# ENET.net
KiCad netlist of a schematic drawn in Altium Designer
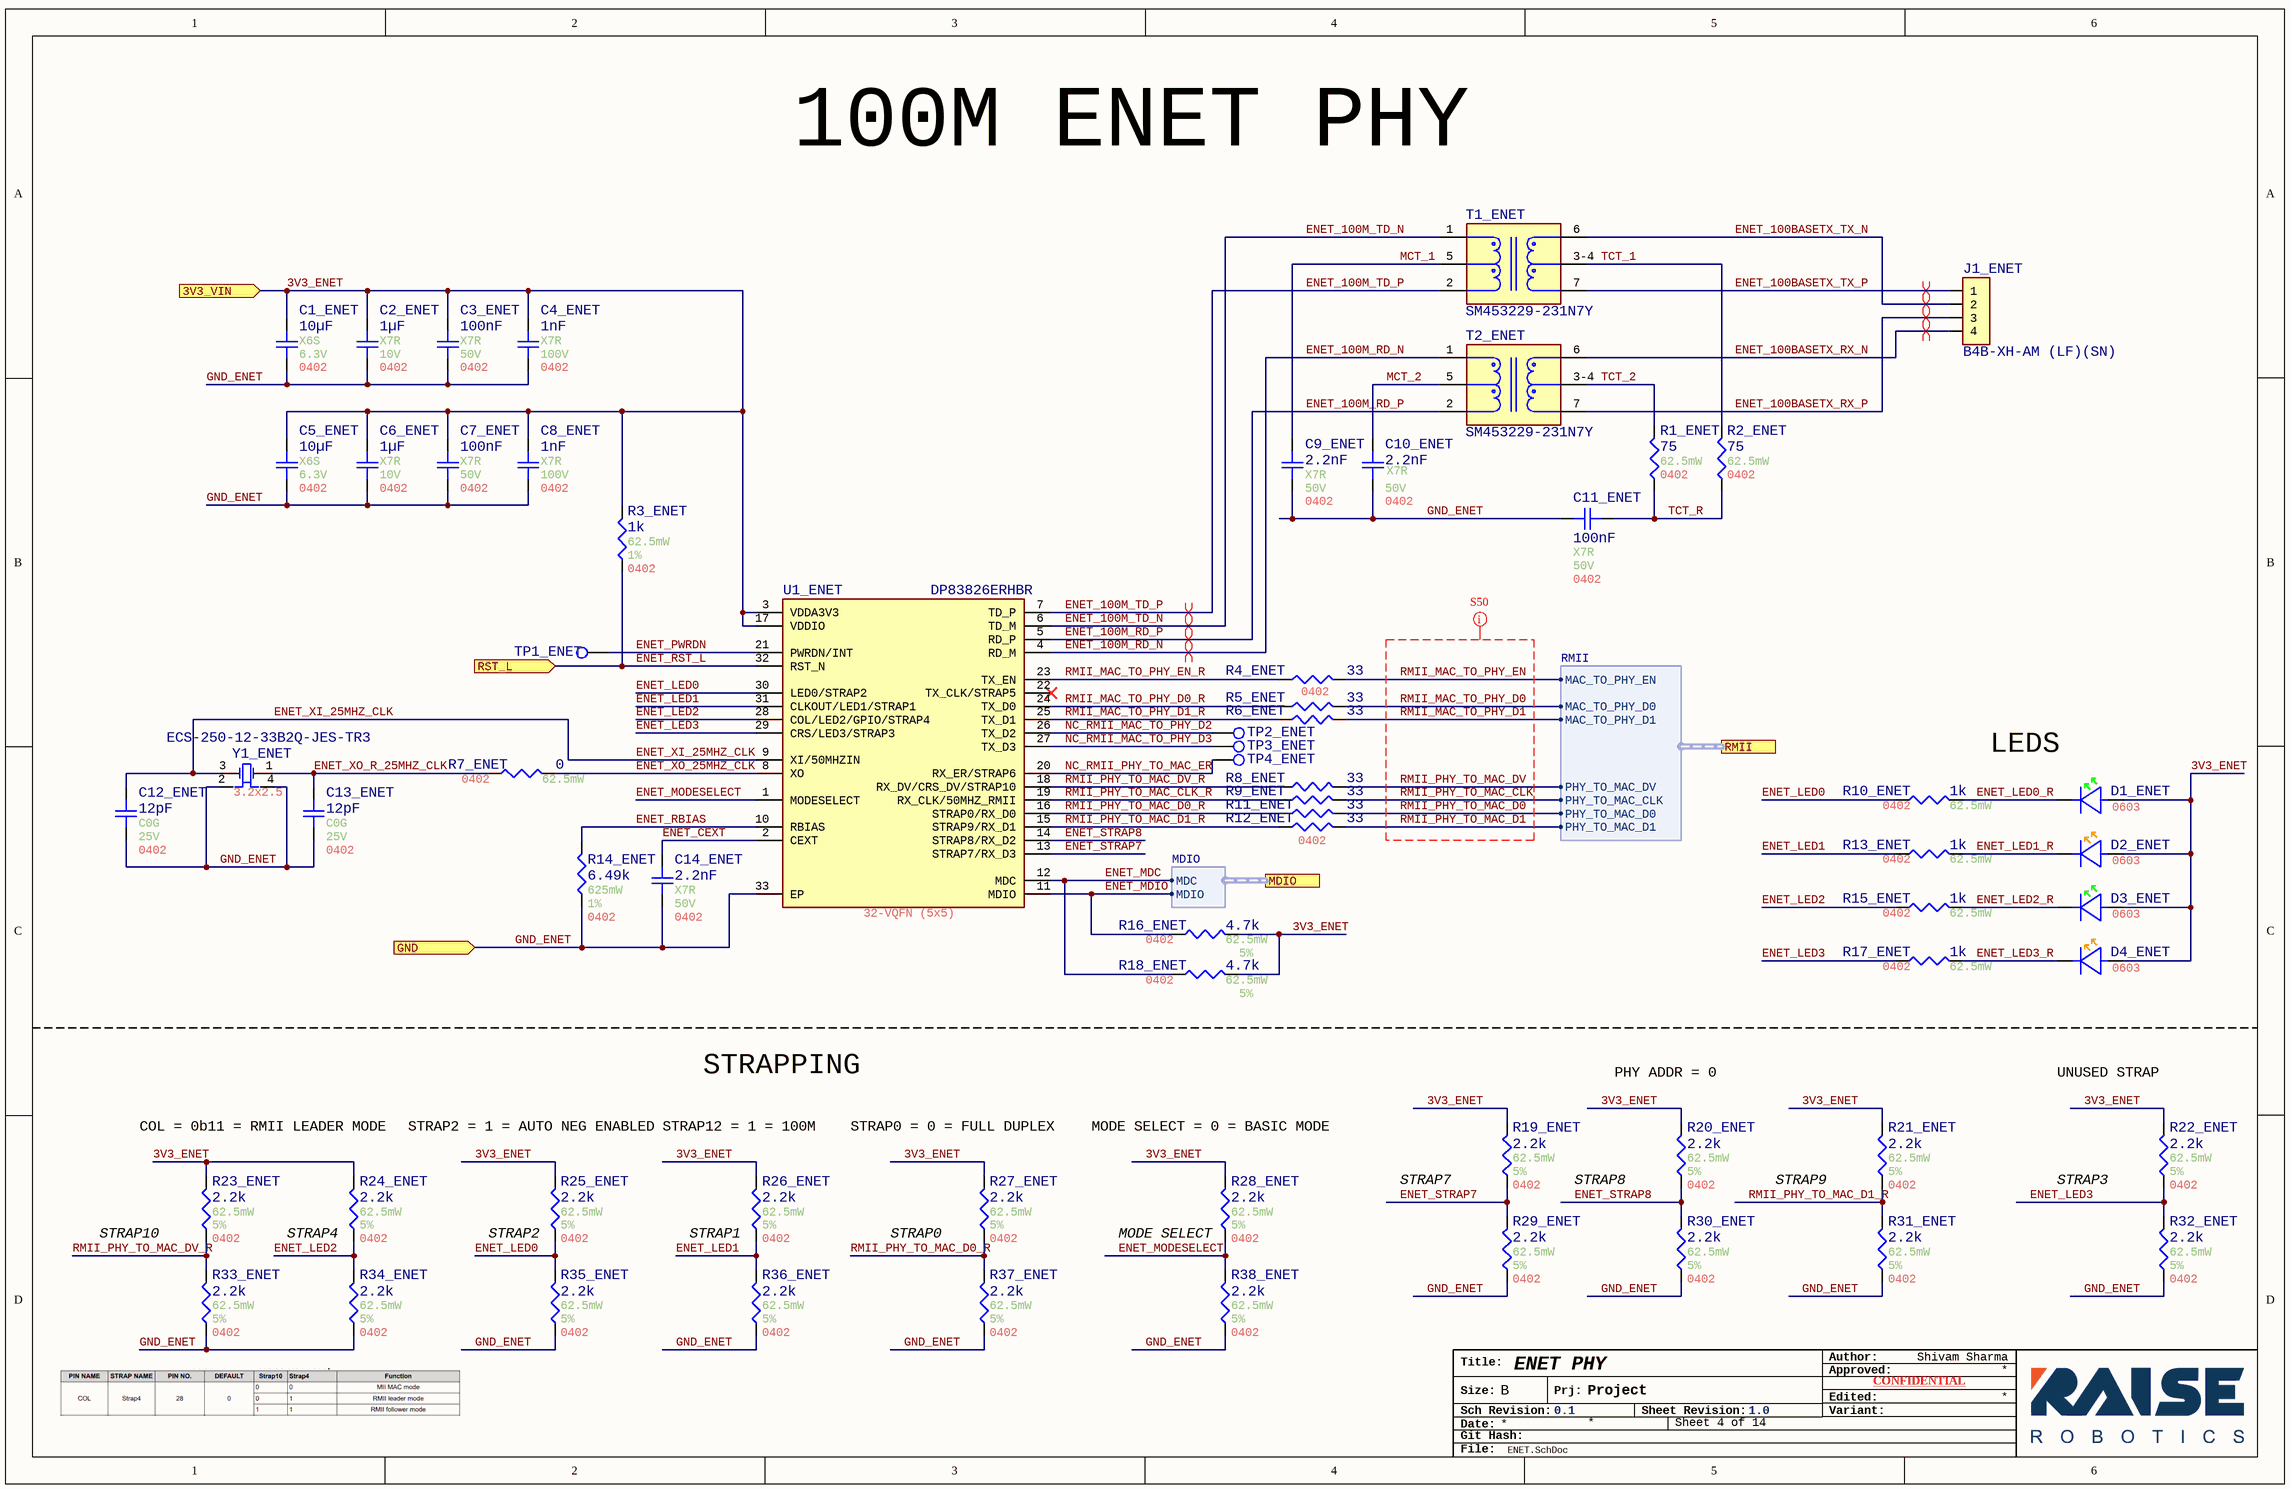
[diagram p0: ENET.SchDoc]

(export (version "E")
  (design (tool "Eeschema 10.0.6"))
  (components
    (comp (ref "C1_ENET")
      (value "10µF")
      (footprint "Generic 0402 capacitor")
      (description "Multilayer Ceramic Capacitors MLCC - SMD/SMT 0402 10uF 6.3VDC 20% X6S AEC-Q200")
      (fields
        (field (name "TEMPERATURE COEFFICIENT") "X6S")
        (field (name "VOLTAGE RATING") "6.3V")
        (field (name "CASE/PACKAGE") "0402")
        (field (name "TOLERANCE") "20%")
        (field (name "Comment") "GRT155C80J106ME13J")
      )
      (libsource (lib "Raise Robotics") (part "Unpolarized Capacitor"))
    )
    (comp (ref "C2_ENET")
      (value "1µF")
      (footprint "Generic 0402 capacitor")
      (description "Cap Cer 1UF 20V X7T 0402")
      (fields
        (field (name "TEMPERATURE COEFFICIENT") "X7R")
        (field (name "VOLTAGE RATING") "10V")
        (field (name "CASE/PACKAGE") "0402")
        (field (name "TOLERANCE") "20%")
        (field (name "Comment") "MAASL105CD7105MFCA01")
      )
      (libsource (lib "Raise Robotics") (part "Unpolarized Capacitor"))
    )
    (comp (ref "C3_ENET")
      (value "100nF")
      (footprint "Generic 0402 capacitor")
      (fields
        (field (name "TEMPERATURE COEFFICIENT") "X7R")
        (field (name "VOLTAGE RATING") "50V")
        (field (name "CASE/PACKAGE") "0402")
        (field (name "TOLERANCE") "10%")
        (field (name "Comment") "GRT155R71H104KE01D")
      )
      (libsource (lib "Raise Robotics") (part "Unpolarized Capacitor"))
    )
    (comp (ref "C4_ENET")
      (value "1nF")
      (footprint "Generic 0402 capacitor")
      (fields
        (field (name "TEMPERATURE COEFFICIENT") "X7R")
        (field (name "VOLTAGE RATING") "100V")
        (field (name "CASE/PACKAGE") "0402")
        (field (name "TOLERANCE") "10%")
        (field (name "Comment") "GCM155R72A102KA37J")
      )
      (libsource (lib "Raise Robotics") (part "Unpolarized Capacitor"))
    )
    (comp (ref "C5_ENET")
      (value "10µF")
      (footprint "Generic 0402 capacitor")
      (description "Multilayer Ceramic Capacitors MLCC - SMD/SMT 0402 10uF 6.3VDC 20% X6S AEC-Q200")
      (fields
        (field (name "TEMPERATURE COEFFICIENT") "X6S")
        (field (name "VOLTAGE RATING") "6.3V")
        (field (name "CASE/PACKAGE") "0402")
        (field (name "TOLERANCE") "20%")
        (field (name "Comment") "GRT155C80J106ME13J")
      )
      (libsource (lib "Raise Robotics") (part "Unpolarized Capacitor"))
    )
    (comp (ref "C6_ENET")
      (value "1µF")
      (footprint "Generic 0402 capacitor")
      (description "Cap Cer 1UF 20V X7T 0402")
      (fields
        (field (name "TEMPERATURE COEFFICIENT") "X7R")
        (field (name "VOLTAGE RATING") "10V")
        (field (name "CASE/PACKAGE") "0402")
        (field (name "TOLERANCE") "20%")
        (field (name "Comment") "MAASL105CD7105MFCA01")
      )
      (libsource (lib "Raise Robotics") (part "Unpolarized Capacitor"))
    )
    (comp (ref "C7_ENET")
      (value "100nF")
      (footprint "Generic 0402 capacitor")
      (fields
        (field (name "TEMPERATURE COEFFICIENT") "X7R")
        (field (name "VOLTAGE RATING") "50V")
        (field (name "CASE/PACKAGE") "0402")
        (field (name "TOLERANCE") "10%")
        (field (name "Comment") "GRT155R71H104KE01D")
      )
      (libsource (lib "Raise Robotics") (part "Unpolarized Capacitor"))
    )
    (comp (ref "C8_ENET")
      (value "1nF")
      (footprint "Generic 0402 capacitor")
      (fields
        (field (name "TEMPERATURE COEFFICIENT") "X7R")
        (field (name "VOLTAGE RATING") "100V")
        (field (name "CASE/PACKAGE") "0402")
        (field (name "TOLERANCE") "10%")
        (field (name "Comment") "GCM155R72A102KA37J")
      )
      (libsource (lib "Raise Robotics") (part "Unpolarized Capacitor"))
    )
    (comp (ref "C9_ENET")
      (value "2.2nF")
      (footprint "Generic 0402 capacitor")
      (description "50V 2.2nF X7R 卤10% 0402 Multilayer Ceramic Capacitors MLCC - SMD/SMT ROHS")
      (fields
        (field (name "TEMPERATURE COEFFICIENT") "X7R")
        (field (name "VOLTAGE RATING") "50V")
        (field (name "CASE/PACKAGE") "0402")
        (field (name "TOLERANCE") "10%")
        (field (name "Comment") "CGA2B2X7R1H222K050BA")
      )
      (libsource (lib "Raise Robotics") (part "Unpolarized Capacitor"))
    )
    (comp (ref "C10_ENET")
      (value "2.2nF")
      (footprint "Generic 0402 capacitor")
      (description "50V 2.2nF X7R 卤10% 0402 Multilayer Ceramic Capacitors MLCC - SMD/SMT ROHS")
      (fields
        (field (name "TEMPERATURE COEFFICIENT") "X7R")
        (field (name "VOLTAGE RATING") "50V")
        (field (name "CASE/PACKAGE") "0402")
        (field (name "TOLERANCE") "10%")
        (field (name "Comment") "CGA2B2X7R1H222K050BA")
      )
      (libsource (lib "Raise Robotics") (part "Unpolarized Capacitor"))
    )
    (comp (ref "C11_ENET")
      (value "100nF")
      (footprint "Generic 0402 capacitor")
      (fields
        (field (name "TEMPERATURE COEFFICIENT") "X7R")
        (field (name "VOLTAGE RATING") "50V")
        (field (name "CASE/PACKAGE") "0402")
        (field (name "TOLERANCE") "10%")
        (field (name "Comment") "GRT155R71H104KE01D")
      )
      (libsource (lib "Raise Robotics") (part "Unpolarized Capacitor"))
    )
    (comp (ref "C12_ENET")
      (value "12pF")
      (footprint "Generic 0402 capacitor")
      (fields
        (field (name "TEMPERATURE COEFFICIENT") "C0G")
        (field (name "VOLTAGE RATING") "25V")
        (field (name "CASE/PACKAGE") "0402")
        (field (name "TOLERANCE") "5%")
        (field (name "Comment") "GRT1555C1E120JA02J")
      )
      (libsource (lib "Raise Robotics") (part "Unpolarized Capacitor"))
    )
    (comp (ref "C13_ENET")
      (value "12pF")
      (footprint "Generic 0402 capacitor")
      (fields
        (field (name "TEMPERATURE COEFFICIENT") "C0G")
        (field (name "VOLTAGE RATING") "25V")
        (field (name "CASE/PACKAGE") "0402")
        (field (name "TOLERANCE") "5%")
        (field (name "Comment") "GRT1555C1E120JA02J")
      )
      (libsource (lib "Raise Robotics") (part "Unpolarized Capacitor"))
    )
    (comp (ref "C14_ENET")
      (value "2.2nF")
      (footprint "Generic 0402 capacitor")
      (description "50V 2.2nF X7R 卤10% 0402 Multilayer Ceramic Capacitors MLCC - SMD/SMT ROHS")
      (fields
        (field (name "TEMPERATURE COEFFICIENT") "X7R")
        (field (name "VOLTAGE RATING") "50V")
        (field (name "CASE/PACKAGE") "0402")
        (field (name "TOLERANCE") "10%")
        (field (name "Comment") "CGA2B2X7R1H222K050BA")
      )
      (libsource (lib "Raise Robotics") (part "Unpolarized Capacitor"))
    )
    (comp (ref "D1_ENET")
      (value "SML-D12P8WT86C")
      (footprint "SML-D12P8WT86C")
      (description "Green 560nm LED Indication - Discrete 2.2V 0603 (1608 Metric)")
      (fields (field (name "CASE/PACKAGE") "0603"))
      (libsource (lib "Raise Robotics") (part "LED Green"))
    )
    (comp (ref "D2_ENET")
      (value "SML-D12D8WT86C")
      (footprint "FP-SML-D12-MFG")
      (description "Orange 605nm LED Indication - Discrete 2.2V 0603 (1608 Metric)")
      (fields (field (name "CASE/PACKAGE") "0603"))
      (libsource (lib "Raise Robotics") (part "LED Orange"))
    )
    (comp (ref "D3_ENET")
      (value "SML-D12P8WT86C")
      (footprint "SML-D12P8WT86C")
      (description "Green 560nm LED Indication - Discrete 2.2V 0603 (1608 Metric)")
      (fields (field (name "CASE/PACKAGE") "0603"))
      (libsource (lib "Raise Robotics") (part "LED Green"))
    )
    (comp (ref "D4_ENET")
      (value "SML-D12D8WT86C")
      (footprint "FP-SML-D12-MFG")
      (description "Orange 605nm LED Indication - Discrete 2.2V 0603 (1608 Metric)")
      (fields (field (name "CASE/PACKAGE") "0603"))
      (libsource (lib "Raise Robotics") (part "LED Orange"))
    )
    (comp (ref "J1_ENET")
      (value "B4B-XH-AM (LF)(SN)")
      (footprint "FP-B4B-XH-AM_LF_SN-MFG")
      (description "Header, Xh, Top, 4Way, 2.5Mm, Boss;")
      (fields (field (name "MANUFACTURER") "JST"))
      (libsource (lib "Raise Robotics") (part "4 pin generic conn"))
    )
    (comp (ref "R1_ENET")
      (value "75")
      (footprint "Generic 0402 Resistor")
      (fields
        (field (name "POWER") "62.5mW")
        (field (name "TOLERANCE") "1%")
        (field (name "CASE/PACKAGE") "0402")
        (field (name "MANUFACTURER PART NUMBER") "Blank")
        (field (name "Comment") "WR04X75R0FTL")
      )
      (libsource (lib "Raise Robotics") (part "Resistor"))
    )
    (comp (ref "R2_ENET")
      (value "75")
      (footprint "Generic 0402 Resistor")
      (fields
        (field (name "POWER") "62.5mW")
        (field (name "TOLERANCE") "1%")
        (field (name "CASE/PACKAGE") "0402")
        (field (name "MANUFACTURER PART NUMBER") "Blank")
        (field (name "Comment") "WR04X75R0FTL")
      )
      (libsource (lib "Raise Robotics") (part "Resistor"))
    )
    (comp (ref "R3_ENET")
      (value "1k")
      (footprint "Generic 0402 Resistor")
      (fields
        (field (name "POWER") "62.5mW")
        (field (name "TOLERANCE") "1%")
        (field (name "CASE/PACKAGE") "0402")
        (field (name "MANUFACTURER PART NUMBER") "Blank")
        (field (name "Comment") "WR04X1001FTL")
      )
      (libsource (lib "Raise Robotics") (part "Resistor"))
    )
    (comp (ref "R4_ENET")
      (value "33")
      (footprint "Generic 0402 Resistor")
      (fields
        (field (name "POWER") "625mW")
        (field (name "TOLERANCE") "1%")
        (field (name "Comment") "RMCA0402FT33R0-HP")
      )
      (libsource (lib "Raise Robotics") (part "Resistor"))
    )
    (comp (ref "R5_ENET")
      (value "33")
      (footprint "Generic 0402 Resistor")
      (fields
        (field (name "POWER") "625mW")
        (field (name "TOLERANCE") "1%")
        (field (name "Comment") "RMCA0402FT33R0-HP")
      )
      (libsource (lib "Raise Robotics") (part "Resistor"))
    )
    (comp (ref "R6_ENET")
      (value "33")
      (footprint "Generic 0402 Resistor")
      (fields
        (field (name "POWER") "625mW")
        (field (name "TOLERANCE") "1%")
        (field (name "CASE/PACKAGE") "0402")
        (field (name "Comment") "RMCA0402FT33R0-HP")
      )
      (libsource (lib "Raise Robotics") (part "Resistor"))
    )
    (comp (ref "R7_ENET")
      (value "0")
      (footprint "Generic 0402 Resistor")
      (description "Fixed Resistor, Metal Glaze/thick Film, 0.0625W, 0ohm, Surface Mount, 0402")
      (fields
        (field (name "POWER") "62.5mW")
        (field (name "TOLERANCE") "0%")
        (field (name "CASE/PACKAGE") "0402")
        (field (name "MANUFACTURER PART NUMBER") "Blank")
      )
      (libsource (lib "Raise Robotics") (part "Resistor"))
    )
    (comp (ref "R8_ENET")
      (value "33")
      (footprint "Generic 0402 Resistor")
      (fields
        (field (name "POWER") "625mW")
        (field (name "TOLERANCE") "1%")
        (field (name "Comment") "RMCA0402FT33R0-HP")
      )
      (libsource (lib "Raise Robotics") (part "Resistor"))
    )
    (comp (ref "R9_ENET")
      (value "33")
      (footprint "Generic 0402 Resistor")
      (fields
        (field (name "POWER") "625mW")
        (field (name "TOLERANCE") "1%")
        (field (name "Comment") "RMCA0402FT33R0-HP")
      )
      (libsource (lib "Raise Robotics") (part "Resistor"))
    )
    (comp (ref "R10_ENET")
      (value "1k")
      (footprint "Generic 0402 Resistor")
      (fields
        (field (name "POWER") "62.5mW")
        (field (name "TOLERANCE") "1%")
        (field (name "CASE/PACKAGE") "0402")
        (field (name "MANUFACTURER PART NUMBER") "Blank")
        (field (name "Comment") "WR04X1001FTL")
      )
      (libsource (lib "Raise Robotics") (part "Resistor"))
    )
    (comp (ref "R11_ENET")
      (value "33")
      (footprint "Generic 0402 Resistor")
      (fields
        (field (name "POWER") "625mW")
        (field (name "TOLERANCE") "1%")
        (field (name "Comment") "RMCA0402FT33R0-HP")
      )
      (libsource (lib "Raise Robotics") (part "Resistor"))
    )
    (comp (ref "R12_ENET")
      (value "33")
      (footprint "Generic 0402 Resistor")
      (fields
        (field (name "POWER") "625mW")
        (field (name "TOLERANCE") "1%")
        (field (name "CASE/PACKAGE") "0402")
        (field (name "Comment") "RMCA0402FT33R0-HP")
      )
      (libsource (lib "Raise Robotics") (part "Resistor"))
    )
    (comp (ref "R13_ENET")
      (value "1k")
      (footprint "Generic 0402 Resistor")
      (fields
        (field (name "POWER") "62.5mW")
        (field (name "TOLERANCE") "1%")
        (field (name "CASE/PACKAGE") "0402")
        (field (name "MANUFACTURER PART NUMBER") "Blank")
        (field (name "Comment") "WR04X1001FTL")
      )
      (libsource (lib "Raise Robotics") (part "Resistor"))
    )
    (comp (ref "R14_ENET")
      (value "6.49k")
      (footprint "Generic 0402 Resistor")
      (fields
        (field (name "POWER") "625mW")
        (field (name "TOLERANCE") "1%")
        (field (name "CASE/PACKAGE") "0402")
        (field (name "Comment") "AC0402FR-076K49L")
      )
      (libsource (lib "Raise Robotics") (part "Resistor"))
    )
    (comp (ref "R15_ENET")
      (value "1k")
      (footprint "Generic 0402 Resistor")
      (fields
        (field (name "POWER") "62.5mW")
        (field (name "TOLERANCE") "1%")
        (field (name "CASE/PACKAGE") "0402")
        (field (name "MANUFACTURER PART NUMBER") "Blank")
        (field (name "Comment") "WR04X1001FTL")
      )
      (libsource (lib "Raise Robotics") (part "Resistor"))
    )
    (comp (ref "R16_ENET")
      (value "4.7k")
      (footprint "Generic 0402 Resistor")
      (fields
        (field (name "POWER") "62.5mW")
        (field (name "TOLERANCE") "5%")
        (field (name "CASE/PACKAGE") "0402")
        (field (name "MANUFACTURER PART NUMBER") "Blank")
        (field (name "Comment") "WR04X472JTL")
      )
      (libsource (lib "Raise Robotics") (part "Resistor"))
    )
    (comp (ref "R17_ENET")
      (value "1k")
      (footprint "Generic 0402 Resistor")
      (fields
        (field (name "POWER") "62.5mW")
        (field (name "TOLERANCE") "1%")
        (field (name "CASE/PACKAGE") "0402")
        (field (name "MANUFACTURER PART NUMBER") "Blank")
        (field (name "Comment") "WR04X1001FTL")
      )
      (libsource (lib "Raise Robotics") (part "Resistor"))
    )
    (comp (ref "R18_ENET")
      (value "4.7k")
      (footprint "Generic 0402 Resistor")
      (fields
        (field (name "POWER") "62.5mW")
        (field (name "TOLERANCE") "5%")
        (field (name "CASE/PACKAGE") "0402")
        (field (name "MANUFACTURER PART NUMBER") "Blank")
        (field (name "Comment") "WR04X472JTL")
      )
      (libsource (lib "Raise Robotics") (part "Resistor"))
    )
    (comp (ref "R19_ENET")
      (value "2.2k")
      (footprint "Generic 0402 Resistor")
      (fields
        (field (name "POWER") "62.5mW")
        (field (name "TOLERANCE") "5%")
        (field (name "CASE/PACKAGE") "0402")
        (field (name "MANUFACTURER PART NUMBER") "Blank")
        (field (name "Comment") "CR0402-JW-222GLF")
      )
      (libsource (lib "Raise Robotics") (part "Resistor"))
    )
    (comp (ref "R20_ENET")
      (value "2.2k")
      (footprint "Generic 0402 Resistor")
      (fields
        (field (name "POWER") "62.5mW")
        (field (name "TOLERANCE") "5%")
        (field (name "CASE/PACKAGE") "0402")
        (field (name "MANUFACTURER PART NUMBER") "Blank")
        (field (name "Comment") "CR0402-JW-222GLF")
      )
      (libsource (lib "Raise Robotics") (part "Resistor"))
    )
    (comp (ref "R21_ENET")
      (value "2.2k")
      (footprint "Generic 0402 Resistor")
      (fields
        (field (name "POWER") "62.5mW")
        (field (name "TOLERANCE") "5%")
        (field (name "CASE/PACKAGE") "0402")
        (field (name "MANUFACTURER PART NUMBER") "Blank")
        (field (name "Comment") "CR0402-JW-222GLF")
      )
      (libsource (lib "Raise Robotics") (part "Resistor"))
    )
    (comp (ref "R22_ENET")
      (value "2.2k")
      (footprint "Generic 0402 Resistor")
      (fields
        (field (name "POWER") "62.5mW")
        (field (name "TOLERANCE") "5%")
        (field (name "CASE/PACKAGE") "0402")
        (field (name "MANUFACTURER PART NUMBER") "Blank")
        (field (name "Comment") "CR0402-JW-222GLF")
      )
      (libsource (lib "Raise Robotics") (part "Resistor"))
    )
    (comp (ref "R23_ENET")
      (value "2.2k")
      (footprint "Generic 0402 Resistor")
      (fields
        (field (name "POWER") "62.5mW")
        (field (name "TOLERANCE") "5%")
        (field (name "CASE/PACKAGE") "0402")
        (field (name "MANUFACTURER PART NUMBER") "Blank")
        (field (name "Comment") "CR0402-JW-222GLF")
      )
      (libsource (lib "Raise Robotics") (part "Resistor"))
    )
    (comp (ref "R24_ENET")
      (value "2.2k")
      (footprint "Generic 0402 Resistor")
      (fields
        (field (name "POWER") "62.5mW")
        (field (name "TOLERANCE") "5%")
        (field (name "CASE/PACKAGE") "0402")
        (field (name "MANUFACTURER PART NUMBER") "Blank")
        (field (name "Comment") "CR0402-JW-222GLF")
      )
      (libsource (lib "Raise Robotics") (part "Resistor"))
    )
    (comp (ref "R25_ENET")
      (value "2.2k")
      (footprint "Generic 0402 Resistor")
      (fields
        (field (name "POWER") "62.5mW")
        (field (name "TOLERANCE") "5%")
        (field (name "CASE/PACKAGE") "0402")
        (field (name "MANUFACTURER PART NUMBER") "Blank")
        (field (name "Comment") "CR0402-JW-222GLF")
      )
      (libsource (lib "Raise Robotics") (part "Resistor"))
    )
    (comp (ref "R26_ENET")
      (value "2.2k")
      (footprint "Generic 0402 Resistor")
      (fields
        (field (name "POWER") "62.5mW")
        (field (name "TOLERANCE") "5%")
        (field (name "CASE/PACKAGE") "0402")
        (field (name "MANUFACTURER PART NUMBER") "Blank")
        (field (name "Comment") "CR0402-JW-222GLF")
      )
      (libsource (lib "Raise Robotics") (part "Resistor"))
    )
    (comp (ref "R27_ENET")
      (value "2.2k")
      (footprint "Generic 0402 Resistor")
      (fields
        (field (name "POWER") "62.5mW")
        (field (name "TOLERANCE") "5%")
        (field (name "CASE/PACKAGE") "0402")
        (field (name "MANUFACTURER PART NUMBER") "Blank")
        (field (name "Comment") "CR0402-JW-222GLF")
      )
      (libsource (lib "Raise Robotics") (part "Resistor"))
    )
    (comp (ref "R28_ENET")
      (value "2.2k")
      (footprint "Generic 0402 Resistor")
      (fields
        (field (name "POWER") "62.5mW")
        (field (name "TOLERANCE") "5%")
        (field (name "CASE/PACKAGE") "0402")
        (field (name "MANUFACTURER PART NUMBER") "Blank")
        (field (name "Comment") "CR0402-JW-222GLF")
      )
      (libsource (lib "Raise Robotics") (part "Resistor"))
    )
    (comp (ref "R29_ENET")
      (value "2.2k")
      (footprint "Generic 0402 Resistor")
      (fields
        (field (name "POWER") "62.5mW")
        (field (name "TOLERANCE") "5%")
        (field (name "CASE/PACKAGE") "0402")
        (field (name "MANUFACTURER PART NUMBER") "Blank")
        (field (name "Comment") "CR0402-JW-222GLF")
      )
      (libsource (lib "Raise Robotics") (part "Resistor"))
    )
    (comp (ref "R30_ENET")
      (value "2.2k")
      (footprint "Generic 0402 Resistor")
      (fields
        (field (name "POWER") "62.5mW")
        (field (name "TOLERANCE") "5%")
        (field (name "CASE/PACKAGE") "0402")
        (field (name "MANUFACTURER PART NUMBER") "Blank")
        (field (name "Comment") "CR0402-JW-222GLF")
      )
      (libsource (lib "Raise Robotics") (part "Resistor"))
    )
    (comp (ref "R31_ENET")
      (value "2.2k")
      (footprint "Generic 0402 Resistor")
      (fields
        (field (name "POWER") "62.5mW")
        (field (name "TOLERANCE") "5%")
        (field (name "CASE/PACKAGE") "0402")
        (field (name "MANUFACTURER PART NUMBER") "Blank")
        (field (name "Comment") "CR0402-JW-222GLF")
      )
      (libsource (lib "Raise Robotics") (part "Resistor"))
    )
    (comp (ref "R32_ENET")
      (value "2.2k")
      (footprint "Generic 0402 Resistor")
      (fields
        (field (name "POWER") "62.5mW")
        (field (name "TOLERANCE") "5%")
        (field (name "CASE/PACKAGE") "0402")
        (field (name "MANUFACTURER PART NUMBER") "Blank")
        (field (name "Comment") "CR0402-JW-222GLF")
      )
      (libsource (lib "Raise Robotics") (part "Resistor"))
    )
    (comp (ref "R33_ENET")
      (value "2.2k")
      (footprint "Generic 0402 Resistor")
      (fields
        (field (name "POWER") "62.5mW")
        (field (name "TOLERANCE") "5%")
        (field (name "CASE/PACKAGE") "0402")
        (field (name "MANUFACTURER PART NUMBER") "Blank")
        (field (name "Comment") "CR0402-JW-222GLF")
      )
      (libsource (lib "Raise Robotics") (part "Resistor"))
    )
    (comp (ref "R34_ENET")
      (value "2.2k")
      (footprint "Generic 0402 Resistor")
      (fields
        (field (name "POWER") "62.5mW")
        (field (name "TOLERANCE") "5%")
        (field (name "CASE/PACKAGE") "0402")
        (field (name "MANUFACTURER PART NUMBER") "Blank")
        (field (name "Comment") "CR0402-JW-222GLF")
      )
      (libsource (lib "Raise Robotics") (part "Resistor"))
    )
    (comp (ref "R35_ENET")
      (value "2.2k")
      (footprint "Generic 0402 Resistor")
      (fields
        (field (name "POWER") "62.5mW")
        (field (name "TOLERANCE") "5%")
        (field (name "CASE/PACKAGE") "0402")
        (field (name "MANUFACTURER PART NUMBER") "Blank")
        (field (name "Comment") "CR0402-JW-222GLF")
      )
      (libsource (lib "Raise Robotics") (part "Resistor"))
    )
    (comp (ref "R36_ENET")
      (value "2.2k")
      (footprint "Generic 0402 Resistor")
      (fields
        (field (name "POWER") "62.5mW")
        (field (name "TOLERANCE") "5%")
        (field (name "CASE/PACKAGE") "0402")
        (field (name "MANUFACTURER PART NUMBER") "Blank")
        (field (name "Comment") "CR0402-JW-222GLF")
      )
      (libsource (lib "Raise Robotics") (part "Resistor"))
    )
    (comp (ref "R37_ENET")
      (value "2.2k")
      (footprint "Generic 0402 Resistor")
      (fields
        (field (name "POWER") "62.5mW")
        (field (name "TOLERANCE") "5%")
        (field (name "CASE/PACKAGE") "0402")
        (field (name "MANUFACTURER PART NUMBER") "Blank")
        (field (name "Comment") "CR0402-JW-222GLF")
      )
      (libsource (lib "Raise Robotics") (part "Resistor"))
    )
    (comp (ref "R38_ENET")
      (value "2.2k")
      (footprint "Generic 0402 Resistor")
      (fields
        (field (name "POWER") "62.5mW")
        (field (name "TOLERANCE") "5%")
        (field (name "CASE/PACKAGE") "0402")
        (field (name "MANUFACTURER PART NUMBER") "Blank")
        (field (name "Comment") "CR0402-JW-222GLF")
      )
      (libsource (lib "Raise Robotics") (part "Resistor"))
    )
    (comp (ref "T1_ENET")
      (value "SM453229-231N7Y")
      (footprint "SM453229-231N7Y")
      (description "CHIP LAN,10/100/1G XFORMER,POE,4")
      (libsource (lib "Raise Robotics") (part "SM453229-231N7Y"))
    )
    (comp (ref "T2_ENET")
      (value "SM453229-231N7Y")
      (footprint "SM453229-231N7Y")
      (description "CHIP LAN,10/100/1G XFORMER,POE,4")
      (libsource (lib "Raise Robotics") (part "SM453229-231N7Y"))
    )
    (comp (ref "TP1_ENET")
      (value "TP 0.75mm")
      (footprint "TP 0.75mm")
      (description "0.75mm circular test point")
      (libsource (lib "Raise Robotics") (part "Test Point"))
    )
    (comp (ref "TP2_ENET")
      (value "TP 0.75mm")
      (footprint "TP 0.75mm")
      (description "0.75mm circular test point")
      (libsource (lib "Raise Robotics") (part "Test Point"))
    )
    (comp (ref "TP3_ENET")
      (value "TP 0.75mm")
      (footprint "TP 0.75mm")
      (description "0.75mm circular test point")
      (libsource (lib "Raise Robotics") (part "Test Point"))
    )
    (comp (ref "TP4_ENET")
      (value "TP 0.75mm")
      (footprint "TP 0.75mm")
      (description "0.75mm circular test point")
      (libsource (lib "Raise Robotics") (part "Test Point"))
    )
    (comp (ref "U1_ENET")
      (value "DP83826ERHBR")
      (footprint "DP83826ERHBR")
      (description "Ethernet Transceiver, 1-Trnsvr, PQCC32")
      (fields (field (name "CASE/PACKAGE") "32-VQFN (5x5)"))
      (libsource (lib "Raise Robotics") (part "DP83826ERHBR"))
    )
    (comp (ref "Y1_ENET")
      (value "ECS-250-12-33B2Q-JES-TR3")
      (footprint "ECS-250-12-33B2Q-JES-TR3")
      (description "Crystal 25.000 Mhz 12PF SMD")
      (fields (field (name "CASE/PACKAGE") "3.2x2.5"))
      (libsource (lib "Raise Robotics") (part "XTAL-2"))
    )
  )
  (nets
    (net (code "3") (name "/3V3_ENET") (class "Default")
      (node (ref "C1_ENET") (pin "2") (pinfunction "2_2") (pintype "passive"))
      (node (ref "C2_ENET") (pin "2") (pinfunction "2_2") (pintype "passive"))
      (node (ref "C3_ENET") (pin "2") (pinfunction "2_2") (pintype "passive"))
      (node (ref "C4_ENET") (pin "2") (pinfunction "2_2") (pintype "passive"))
      (node (ref "C5_ENET") (pin "2") (pinfunction "2_2") (pintype "passive"))
      (node (ref "C6_ENET") (pin "2") (pinfunction "2_2") (pintype "passive"))
      (node (ref "C7_ENET") (pin "2") (pinfunction "2_2") (pintype "passive"))
      (node (ref "C8_ENET") (pin "2") (pinfunction "2_2") (pintype "passive"))
      (node (ref "D1_ENET") (pin "2") (pinfunction "A_2") (pintype "passive"))
      (node (ref "D2_ENET") (pin "2") (pinfunction "A_2") (pintype "passive"))
      (node (ref "D3_ENET") (pin "2") (pinfunction "A_2") (pintype "passive"))
      (node (ref "D4_ENET") (pin "2") (pinfunction "A_2") (pintype "passive"))
      (node (ref "R16_ENET") (pin "2") (pinfunction "2_2") (pintype "passive"))
      (node (ref "R18_ENET") (pin "2") (pinfunction "2_2") (pintype "passive"))
      (node (ref "R19_ENET") (pin "2") (pinfunction "2_2") (pintype "passive"))
      (node (ref "R20_ENET") (pin "2") (pinfunction "2_2") (pintype "passive"))
      (node (ref "R21_ENET") (pin "2") (pinfunction "2_2") (pintype "passive"))
      (node (ref "R22_ENET") (pin "2") (pinfunction "2_2") (pintype "passive"))
      (node (ref "R23_ENET") (pin "2") (pinfunction "2_2") (pintype "passive"))
      (node (ref "R24_ENET") (pin "2") (pinfunction "2_2") (pintype "passive"))
      (node (ref "R25_ENET") (pin "2") (pinfunction "2_2") (pintype "passive"))
      (node (ref "R26_ENET") (pin "2") (pinfunction "2_2") (pintype "passive"))
      (node (ref "R27_ENET") (pin "2") (pinfunction "2_2") (pintype "passive"))
      (node (ref "R28_ENET") (pin "2") (pinfunction "2_2") (pintype "passive"))
      (node (ref "R3_ENET") (pin "2") (pinfunction "2_2") (pintype "passive"))
      (node (ref "U1_ENET") (pin "17") (pinfunction "VDDIO_17") (pintype "passive"))
      (node (ref "U1_ENET") (pin "3") (pinfunction "VDDA3V3_3") (pintype "passive"))
    )
    (net (code "4") (name "/ENET_100BASETX_RX_N") (class "Default")
      (node (ref "J1_ENET") (pin "4") (pinfunction "4_4") (pintype "passive"))
      (node (ref "T2_ENET") (pin "6") (pinfunction "6_6") (pintype "passive"))
    )
    (net (code "5") (name "/ENET_100BASETX_RX_P") (class "Default")
      (node (ref "J1_ENET") (pin "3") (pinfunction "3_3") (pintype "passive"))
      (node (ref "T2_ENET") (pin "7") (pinfunction "7_7") (pintype "passive"))
    )
    (net (code "6") (name "/ENET_100BASETX_TX_N") (class "Default")
      (node (ref "J1_ENET") (pin "2") (pinfunction "2_2") (pintype "passive"))
      (node (ref "T1_ENET") (pin "6") (pinfunction "6_6") (pintype "passive"))
    )
    (net (code "7") (name "/ENET_100BASETX_TX_P") (class "Default")
      (node (ref "J1_ENET") (pin "1") (pinfunction "1_1") (pintype "passive"))
      (node (ref "T1_ENET") (pin "7") (pinfunction "7_7") (pintype "passive"))
    )
    (net (code "8") (name "/ENET_100M_RD_N") (class "Default")
      (node (ref "T2_ENET") (pin "1") (pinfunction "1_1") (pintype "passive"))
      (node (ref "U1_ENET") (pin "4") (pinfunction "RD_M_4") (pintype "passive"))
    )
    (net (code "9") (name "/ENET_100M_RD_P") (class "Default")
      (node (ref "T2_ENET") (pin "2") (pinfunction "2_2") (pintype "passive"))
      (node (ref "U1_ENET") (pin "5") (pinfunction "RD_P_5") (pintype "passive"))
    )
    (net (code "10") (name "/ENET_100M_TD_N") (class "Default")
      (node (ref "T1_ENET") (pin "1") (pinfunction "1_1") (pintype "passive"))
      (node (ref "U1_ENET") (pin "6") (pinfunction "TD_M_6") (pintype "passive"))
    )
    (net (code "11") (name "/ENET_100M_TD_P") (class "Default")
      (node (ref "T1_ENET") (pin "2") (pinfunction "2_2") (pintype "passive"))
      (node (ref "U1_ENET") (pin "7") (pinfunction "TD_P_7") (pintype "passive"))
    )
    (net (code "12") (name "/ENET_CEXT") (class "Default")
      (node (ref "C14_ENET") (pin "2") (pinfunction "2_2") (pintype "passive"))
      (node (ref "U1_ENET") (pin "2") (pinfunction "CEXT_2") (pintype "passive"))
    )
    (net (code "13") (name "/ENET_LED0") (class "Default")
      (node (ref "R10_ENET") (pin "1") (pinfunction "1_1") (pintype "passive"))
      (node (ref "R25_ENET") (pin "1") (pinfunction "1_1") (pintype "passive"))
      (node (ref "R35_ENET") (pin "2") (pinfunction "2_2") (pintype "passive"))
      (node (ref "U1_ENET") (pin "30") (pinfunction "LED0/STRAP2_30") (pintype "passive"))
    )
    (net (code "14") (name "/ENET_LED0_R") (class "Default")
      (node (ref "D1_ENET") (pin "1") (pinfunction "C_1") (pintype "passive"))
      (node (ref "R10_ENET") (pin "2") (pinfunction "2_2") (pintype "passive"))
    )
    (net (code "15") (name "/ENET_LED1") (class "Default")
      (node (ref "R13_ENET") (pin "1") (pinfunction "1_1") (pintype "passive"))
      (node (ref "R26_ENET") (pin "1") (pinfunction "1_1") (pintype "passive"))
      (node (ref "R36_ENET") (pin "2") (pinfunction "2_2") (pintype "passive"))
      (node (ref "U1_ENET") (pin "31") (pinfunction "CLKOUT/LED1/STRAP1_31") (pintype "passive"))
    )
    (net (code "16") (name "/ENET_LED1_R") (class "Default")
      (node (ref "D2_ENET") (pin "1") (pinfunction "C_1") (pintype "passive"))
      (node (ref "R13_ENET") (pin "2") (pinfunction "2_2") (pintype "passive"))
    )
    (net (code "17") (name "/ENET_LED2") (class "Default")
      (node (ref "R15_ENET") (pin "1") (pinfunction "1_1") (pintype "passive"))
      (node (ref "R24_ENET") (pin "1") (pinfunction "1_1") (pintype "passive"))
      (node (ref "R34_ENET") (pin "2") (pinfunction "2_2") (pintype "passive"))
      (node (ref "U1_ENET") (pin "28") (pinfunction "COL/LED2/GPIO/STRAP4_28") (pintype "passive"))
    )
    (net (code "18") (name "/ENET_LED2_R") (class "Default")
      (node (ref "D3_ENET") (pin "1") (pinfunction "C_1") (pintype "passive"))
      (node (ref "R15_ENET") (pin "2") (pinfunction "2_2") (pintype "passive"))
    )
    (net (code "19") (name "/ENET_LED3") (class "Default")
      (node (ref "R17_ENET") (pin "1") (pinfunction "1_1") (pintype "passive"))
      (node (ref "R22_ENET") (pin "1") (pinfunction "1_1") (pintype "passive"))
      (node (ref "R32_ENET") (pin "2") (pinfunction "2_2") (pintype "passive"))
      (node (ref "U1_ENET") (pin "29") (pinfunction "CRS/LED3/STRAP3_29") (pintype "passive"))
    )
    (net (code "20") (name "/ENET_LED3_R") (class "Default")
      (node (ref "D4_ENET") (pin "1") (pinfunction "C_1") (pintype "passive"))
      (node (ref "R17_ENET") (pin "2") (pinfunction "2_2") (pintype "passive"))
    )
    (net (code "21") (name "/ENET_MDC") (class "Default")
      (node (ref "R18_ENET") (pin "1") (pinfunction "1_1") (pintype "passive"))
      (node (ref "U1_ENET") (pin "12") (pinfunction "MDC_12") (pintype "passive"))
    )
    (net (code "22") (name "/ENET_MDIO") (class "Default")
      (node (ref "R16_ENET") (pin "1") (pinfunction "1_1") (pintype "passive"))
      (node (ref "U1_ENET") (pin "11") (pinfunction "MDIO_11") (pintype "passive"))
    )
    (net (code "23") (name "/ENET_MODESELECT") (class "Default")
      (node (ref "R28_ENET") (pin "1") (pinfunction "1_1") (pintype "passive"))
      (node (ref "R38_ENET") (pin "2") (pinfunction "2_2") (pintype "passive"))
      (node (ref "U1_ENET") (pin "1") (pinfunction "MODESELECT_1") (pintype "passive"))
    )
    (net (code "24") (name "/ENET_PWRDN") (class "Default")
      (node (ref "TP1_ENET") (pin "1") (pinfunction "1_1") (pintype "passive"))
      (node (ref "U1_ENET") (pin "21") (pinfunction "PWRDN/INT_21") (pintype "passive"))
    )
    (net (code "25") (name "/ENET_RBIAS") (class "Default")
      (node (ref "R14_ENET") (pin "2") (pinfunction "2_2") (pintype "passive"))
      (node (ref "U1_ENET") (pin "10") (pinfunction "RBIAS_10") (pintype "passive"))
    )
    (net (code "26") (name "/ENET_RST_L") (class "Default")
      (node (ref "R3_ENET") (pin "1") (pinfunction "1_1") (pintype "passive"))
      (node (ref "U1_ENET") (pin "32") (pinfunction "RST_N_32") (pintype "passive"))
    )
    (net (code "27") (name "/ENET_STRAP7") (class "Default")
      (node (ref "R19_ENET") (pin "1") (pinfunction "1_1") (pintype "passive"))
      (node (ref "R29_ENET") (pin "2") (pinfunction "2_2") (pintype "passive"))
      (node (ref "U1_ENET") (pin "13") (pinfunction "STRAP7/RX_D3_13") (pintype "passive"))
    )
    (net (code "28") (name "/ENET_STRAP8") (class "Default")
      (node (ref "R20_ENET") (pin "1") (pinfunction "1_1") (pintype "passive"))
      (node (ref "R30_ENET") (pin "2") (pinfunction "2_2") (pintype "passive"))
      (node (ref "U1_ENET") (pin "14") (pinfunction "STRAP8/RX_D2_14") (pintype "passive"))
    )
    (net (code "29") (name "/ENET_XI_25MHZ_CLK") (class "Default")
      (node (ref "C12_ENET") (pin "2") (pinfunction "2_2") (pintype "passive"))
      (node (ref "U1_ENET") (pin "9") (pinfunction "XI/50MHZIN_9") (pintype "passive"))
      (node (ref "Y1_ENET") (pin "3") (pinfunction "3_3") (pintype "passive"))
    )
    (net (code "30") (name "/ENET_XO_25MHZ_CLK") (class "Default")
      (node (ref "R7_ENET") (pin "2") (pinfunction "2_2") (pintype "passive"))
      (node (ref "U1_ENET") (pin "8") (pinfunction "XO_8") (pintype "passive"))
    )
    (net (code "31") (name "/ENET_XO_R_25MHZ_CLK") (class "Default")
      (node (ref "C13_ENET") (pin "2") (pinfunction "2_2") (pintype "passive"))
      (node (ref "R7_ENET") (pin "1") (pinfunction "1_1") (pintype "passive"))
      (node (ref "Y1_ENET") (pin "1") (pinfunction "1_1") (pintype "passive"))
    )
    (net (code "32") (name "/GND_ENET") (class "Default")
      (node (ref "C10_ENET") (pin "1") (pinfunction "1_1") (pintype "passive"))
      (node (ref "C11_ENET") (pin "2") (pinfunction "2_2") (pintype "passive"))
      (node (ref "C12_ENET") (pin "1") (pinfunction "1_1") (pintype "passive"))
      (node (ref "C13_ENET") (pin "1") (pinfunction "1_1") (pintype "passive"))
      (node (ref "C14_ENET") (pin "1") (pinfunction "1_1") (pintype "passive"))
      (node (ref "C1_ENET") (pin "1") (pinfunction "1_1") (pintype "passive"))
      (node (ref "C2_ENET") (pin "1") (pinfunction "1_1") (pintype "passive"))
      (node (ref "C3_ENET") (pin "1") (pinfunction "1_1") (pintype "passive"))
      (node (ref "C4_ENET") (pin "1") (pinfunction "1_1") (pintype "passive"))
      (node (ref "C5_ENET") (pin "1") (pinfunction "1_1") (pintype "passive"))
      (node (ref "C6_ENET") (pin "1") (pinfunction "1_1") (pintype "passive"))
      (node (ref "C7_ENET") (pin "1") (pinfunction "1_1") (pintype "passive"))
      (node (ref "C8_ENET") (pin "1") (pinfunction "1_1") (pintype "passive"))
      (node (ref "C9_ENET") (pin "1") (pinfunction "1_1") (pintype "passive"))
      (node (ref "R14_ENET") (pin "1") (pinfunction "1_1") (pintype "passive"))
      (node (ref "R29_ENET") (pin "1") (pinfunction "1_1") (pintype "passive"))
      (node (ref "R30_ENET") (pin "1") (pinfunction "1_1") (pintype "passive"))
      (node (ref "R31_ENET") (pin "1") (pinfunction "1_1") (pintype "passive"))
      (node (ref "R32_ENET") (pin "1") (pinfunction "1_1") (pintype "passive"))
      (node (ref "R33_ENET") (pin "1") (pinfunction "1_1") (pintype "passive"))
      (node (ref "R34_ENET") (pin "1") (pinfunction "1_1") (pintype "passive"))
      (node (ref "R35_ENET") (pin "1") (pinfunction "1_1") (pintype "passive"))
      (node (ref "R36_ENET") (pin "1") (pinfunction "1_1") (pintype "passive"))
      (node (ref "R37_ENET") (pin "1") (pinfunction "1_1") (pintype "passive"))
      (node (ref "R38_ENET") (pin "1") (pinfunction "1_1") (pintype "passive"))
      (node (ref "U1_ENET") (pin "33") (pinfunction "EP_33") (pintype "passive"))
      (node (ref "Y1_ENET") (pin "2") (pinfunction "2_2") (pintype "passive"))
      (node (ref "Y1_ENET") (pin "4") (pinfunction "4_4") (pintype "passive"))
    )
    (net (code "33") (name "/MCT_1") (class "Default")
      (node (ref "C9_ENET") (pin "2") (pinfunction "2_2") (pintype "passive"))
      (node (ref "T1_ENET") (pin "5") (pinfunction "5_5") (pintype "passive"))
    )
    (net (code "34") (name "/MCT_2") (class "Default")
      (node (ref "C10_ENET") (pin "2") (pinfunction "2_2") (pintype "passive"))
      (node (ref "T2_ENET") (pin "5") (pinfunction "5_5") (pintype "passive"))
    )
    (net (code "35") (name "/NC_RMII_MAC_TO_PHY_D2") (class "Default")
      (node (ref "TP2_ENET") (pin "1") (pinfunction "1_1") (pintype "passive"))
      (node (ref "U1_ENET") (pin "26") (pinfunction "TX_D2_26") (pintype "passive"))
    )
    (net (code "36") (name "/NC_RMII_MAC_TO_PHY_D3") (class "Default")
      (node (ref "TP3_ENET") (pin "1") (pinfunction "1_1") (pintype "passive"))
      (node (ref "U1_ENET") (pin "27") (pinfunction "TX_D3_27") (pintype "passive"))
    )
    (net (code "37") (name "/NC_RMII_PHY_TO_MAC_ER") (class "Default")
      (node (ref "TP4_ENET") (pin "1") (pinfunction "1_1") (pintype "passive"))
      (node (ref "U1_ENET") (pin "20") (pinfunction "RX_ER/STRAP6_20") (pintype "passive"))
    )
    (net (code "38") (name "/RMII_MAC_TO_PHY_D0") (class "Default")
      (node (ref "R5_ENET") (pin "2") (pinfunction "2_2") (pintype "passive"))
    )
    (net (code "39") (name "/RMII_MAC_TO_PHY_D0_R") (class "Default")
      (node (ref "R5_ENET") (pin "1") (pinfunction "1_1") (pintype "passive"))
      (node (ref "U1_ENET") (pin "24") (pinfunction "TX_D0_24") (pintype "passive"))
    )
    (net (code "40") (name "/RMII_MAC_TO_PHY_D1") (class "Default")
      (node (ref "R6_ENET") (pin "2") (pinfunction "2_2") (pintype "passive"))
    )
    (net (code "41") (name "/RMII_MAC_TO_PHY_D1_R") (class "Default")
      (node (ref "R6_ENET") (pin "1") (pinfunction "1_1") (pintype "passive"))
      (node (ref "U1_ENET") (pin "25") (pinfunction "TX_D1_25") (pintype "passive"))
    )
    (net (code "42") (name "/RMII_MAC_TO_PHY_EN") (class "Default")
      (node (ref "R4_ENET") (pin "2") (pinfunction "2_2") (pintype "passive"))
    )
    (net (code "43") (name "/RMII_MAC_TO_PHY_EN_R") (class "Default")
      (node (ref "R4_ENET") (pin "1") (pinfunction "1_1") (pintype "passive"))
      (node (ref "U1_ENET") (pin "23") (pinfunction "TX_EN_23") (pintype "passive"))
    )
    (net (code "44") (name "/RMII_PHY_TO_MAC_CLK") (class "Default")
      (node (ref "R9_ENET") (pin "2") (pinfunction "2_2") (pintype "passive"))
    )
    (net (code "45") (name "/RMII_PHY_TO_MAC_CLK_R") (class "Default")
      (node (ref "R9_ENET") (pin "1") (pinfunction "1_1") (pintype "passive"))
      (node (ref "U1_ENET") (pin "19") (pinfunction "RX_CLK/50MHZ_RMII_19") (pintype "passive"))
    )
    (net (code "46") (name "/RMII_PHY_TO_MAC_D0") (class "Default")
      (node (ref "R11_ENET") (pin "2") (pinfunction "2_2") (pintype "passive"))
    )
    (net (code "47") (name "/RMII_PHY_TO_MAC_D0_R") (class "Default")
      (node (ref "R11_ENET") (pin "1") (pinfunction "1_1") (pintype "passive"))
      (node (ref "R27_ENET") (pin "1") (pinfunction "1_1") (pintype "passive"))
      (node (ref "R37_ENET") (pin "2") (pinfunction "2_2") (pintype "passive"))
      (node (ref "U1_ENET") (pin "16") (pinfunction "STRAP0/RX_D0_16") (pintype "passive"))
    )
    (net (code "48") (name "/RMII_PHY_TO_MAC_D1") (class "Default")
      (node (ref "R12_ENET") (pin "2") (pinfunction "2_2") (pintype "passive"))
    )
    (net (code "49") (name "/RMII_PHY_TO_MAC_D1_R") (class "Default")
      (node (ref "R12_ENET") (pin "1") (pinfunction "1_1") (pintype "passive"))
      (node (ref "R21_ENET") (pin "1") (pinfunction "1_1") (pintype "passive"))
      (node (ref "R31_ENET") (pin "2") (pinfunction "2_2") (pintype "passive"))
      (node (ref "U1_ENET") (pin "15") (pinfunction "STRAP9/RX_D1_15") (pintype "passive"))
    )
    (net (code "50") (name "/RMII_PHY_TO_MAC_DV") (class "Default")
      (node (ref "R8_ENET") (pin "2") (pinfunction "2_2") (pintype "passive"))
    )
    (net (code "51") (name "/RMII_PHY_TO_MAC_DV_R") (class "Default")
      (node (ref "R23_ENET") (pin "1") (pinfunction "1_1") (pintype "passive"))
      (node (ref "R33_ENET") (pin "2") (pinfunction "2_2") (pintype "passive"))
      (node (ref "R8_ENET") (pin "1") (pinfunction "1_1") (pintype "passive"))
      (node (ref "U1_ENET") (pin "18") (pinfunction "RX_DV/CRS_DV/STRAP10_18") (pintype "passive"))
    )
    (net (code "52") (name "/TCT_1") (class "Default")
      (node (ref "R2_ENET") (pin "2") (pinfunction "2_2") (pintype "passive"))
      (node (ref "T1_ENET") (pin "3-4") (pinfunction "3-4_3-4") (pintype "passive"))
    )
    (net (code "53") (name "/TCT_2") (class "Default")
      (node (ref "R1_ENET") (pin "2") (pinfunction "2_2") (pintype "passive"))
      (node (ref "T2_ENET") (pin "3-4") (pinfunction "3-4_3-4") (pintype "passive"))
    )
    (net (code "54") (name "/TCT_R") (class "Default")
      (node (ref "C11_ENET") (pin "1") (pinfunction "1_1") (pintype "passive"))
      (node (ref "R1_ENET") (pin "1") (pinfunction "1_1") (pintype "passive"))
      (node (ref "R2_ENET") (pin "1") (pinfunction "1_1") (pintype "passive"))
    )
    (net (code "57") (name "unconnected-(U1_ENET-TX_CLK{slash}STRAP5-Pad22)") (class "Default")
      (node (ref "U1_ENET") (pin "22") (pinfunction "TX_CLK/STRAP5_22") (pintype "passive+no_connect"))
    )
  )
)
